# PCIe.net
KiCad netlist of a schematic drawn in Altium Designer
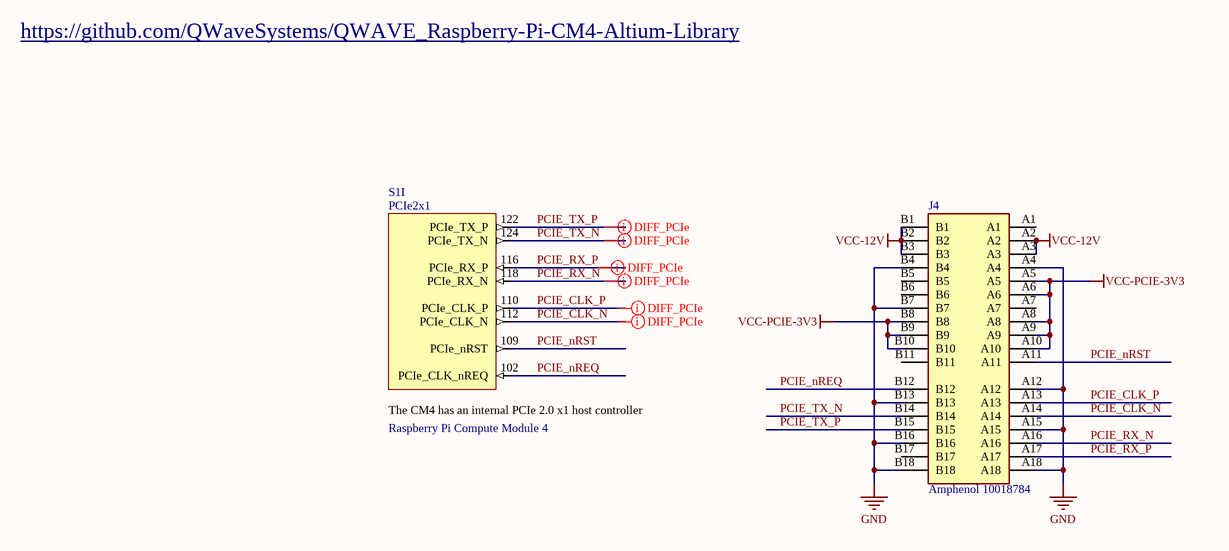
[diagram p0: PCIe.SchDoc]

(export (version "E")
  (design (tool "Eeschema 10.0.6"))
  (components
    (comp (ref "J4")
      (value "Amphenol 10018784")
      (footprint "PCIE-1X-Connector")
      (description "36 Position Female Connector Amphenol 10018784-10210TLF")
      (fields (field (name "MP") "10018784-10210TLF") (field (name "MF") "Amphenol ICC"))
      (libsource (lib "MyPcbLib") (part "PCIE-1X-Connector"))
    )
    (comp (ref "S1")
      (value "Raspberry Pi Compute Module 4")
      (footprint "CM4-F40C-100DS-0.4v_1.5mm_0mm")
      (description "Raspberry Pi Compute Module 4 by Amornthep Phunsin")
      (libsource (lib "SOM") (part "CM4"))
    )
  )
  (nets
    (net (code "1") (name "/PCIE_CLK_N") (class "Default")
      (node (ref "J4") (pin "A14") (pinfunction "A14_A14") (pintype "passive"))
      (node (ref "S1") (pin "112") (pinfunction "PCIe_CLK_N_112") (pintype "output"))
    )
    (net (code "2") (name "/PCIE_CLK_P") (class "Default")
      (node (ref "J4") (pin "A13") (pinfunction "A13_A13") (pintype "passive"))
      (node (ref "S1") (pin "110") (pinfunction "PCIe_CLK_P_110") (pintype "output"))
    )
    (net (code "3") (name "/PCIE_RX_N") (class "Default")
      (node (ref "J4") (pin "A16") (pinfunction "A16_A16") (pintype "passive"))
      (node (ref "S1") (pin "118") (pinfunction "PCIe_RX_N_118") (pintype "input"))
    )
    (net (code "4") (name "/PCIE_RX_P") (class "Default")
      (node (ref "J4") (pin "A17") (pinfunction "A17_A17") (pintype "passive"))
      (node (ref "S1") (pin "116") (pinfunction "PCIe_RX_P_116") (pintype "input"))
    )
    (net (code "5") (name "/PCIE_TX_N") (class "Default")
      (node (ref "J4") (pin "B14") (pinfunction "B14_B14") (pintype "passive"))
      (node (ref "S1") (pin "124") (pinfunction "PCIe_TX_N_124") (pintype "output"))
    )
    (net (code "6") (name "/PCIE_TX_P") (class "Default")
      (node (ref "J4") (pin "B15") (pinfunction "B15_B15") (pintype "passive"))
      (node (ref "S1") (pin "122") (pinfunction "PCIe_TX_P_122") (pintype "output"))
    )
    (net (code "7") (name "/PCIE_nREQ") (class "Default")
      (node (ref "J4") (pin "B12") (pinfunction "B12_B12") (pintype "passive"))
      (node (ref "S1") (pin "102") (pinfunction "PCIe_CLK_nREQ_102") (pintype "input"))
    )
    (net (code "8") (name "/PCIE_nRST") (class "Default")
      (node (ref "J4") (pin "A11") (pinfunction "A11_A11") (pintype "passive"))
      (node (ref "S1") (pin "109") (pinfunction "PCIe_nRST_109") (pintype "output"))
    )
    (net (code "9") (name "GND") (class "Default")
      (node (ref "J4") (pin "A12") (pinfunction "A12_A12") (pintype "passive"))
      (node (ref "J4") (pin "A15") (pinfunction "A15_A15") (pintype "passive"))
      (node (ref "J4") (pin "A18") (pinfunction "A18_A18") (pintype "passive"))
      (node (ref "J4") (pin "A4") (pinfunction "A4_A4") (pintype "passive"))
      (node (ref "J4") (pin "B13") (pinfunction "B13_B13") (pintype "passive"))
      (node (ref "J4") (pin "B16") (pinfunction "B16_B16") (pintype "passive"))
      (node (ref "J4") (pin "B18") (pinfunction "B18_B18") (pintype "passive"))
      (node (ref "J4") (pin "B4") (pinfunction "B4_B4") (pintype "passive"))
      (node (ref "J4") (pin "B7") (pinfunction "B7_B7") (pintype "passive"))
    )
    (net (code "10") (name "VCC-12V") (class "Default")
      (node (ref "J4") (pin "A2") (pinfunction "A2_A2") (pintype "passive"))
      (node (ref "J4") (pin "A3") (pinfunction "A3_A3") (pintype "passive"))
      (node (ref "J4") (pin "B1") (pinfunction "B1_B1") (pintype "passive"))
      (node (ref "J4") (pin "B2") (pinfunction "B2_B2") (pintype "passive"))
      (node (ref "J4") (pin "B3") (pinfunction "B3_B3") (pintype "passive"))
    )
    (net (code "11") (name "VCC-PCIE-3V3") (class "Default")
      (node (ref "J4") (pin "A10") (pinfunction "A10_A10") (pintype "passive"))
      (node (ref "J4") (pin "A5") (pinfunction "A5_A5") (pintype "passive"))
      (node (ref "J4") (pin "A6") (pinfunction "A6_A6") (pintype "passive"))
      (node (ref "J4") (pin "A8") (pinfunction "A8_A8") (pintype "passive"))
      (node (ref "J4") (pin "A9") (pinfunction "A9_A9") (pintype "passive"))
      (node (ref "J4") (pin "B10") (pinfunction "B10_B10") (pintype "passive"))
      (node (ref "J4") (pin "B8") (pinfunction "B8_B8") (pintype "passive"))
      (node (ref "J4") (pin "B9") (pinfunction "B9_B9") (pintype "passive"))
    )
    (net (code "12") (name "unconnected-(J4-PadA1)") (class "Default")
      (node (ref "J4") (pin "A1") (pinfunction "A1_A1") (pintype "passive"))
    )
    (net (code "13") (name "unconnected-(J4-PadA7)") (class "Default")
      (node (ref "J4") (pin "A7") (pinfunction "A7_A7") (pintype "passive"))
    )
    (net (code "14") (name "unconnected-(J4-PadB5)") (class "Default")
      (node (ref "J4") (pin "B5") (pinfunction "B5_B5") (pintype "passive"))
    )
    (net (code "15") (name "unconnected-(J4-PadB6)") (class "Default")
      (node (ref "J4") (pin "B6") (pinfunction "B6_B6") (pintype "passive"))
    )
    (net (code "16") (name "unconnected-(J4-PadB11)") (class "Default")
      (node (ref "J4") (pin "B11") (pinfunction "B11_B11") (pintype "passive"))
    )
    (net (code "17") (name "unconnected-(J4-PadB17)") (class "Default")
      (node (ref "J4") (pin "B17") (pinfunction "B17_B17") (pintype "passive"))
    )
  )
)
